# LCD_Button_LED.net
KiCad netlist of a schematic drawn in Altium Designer
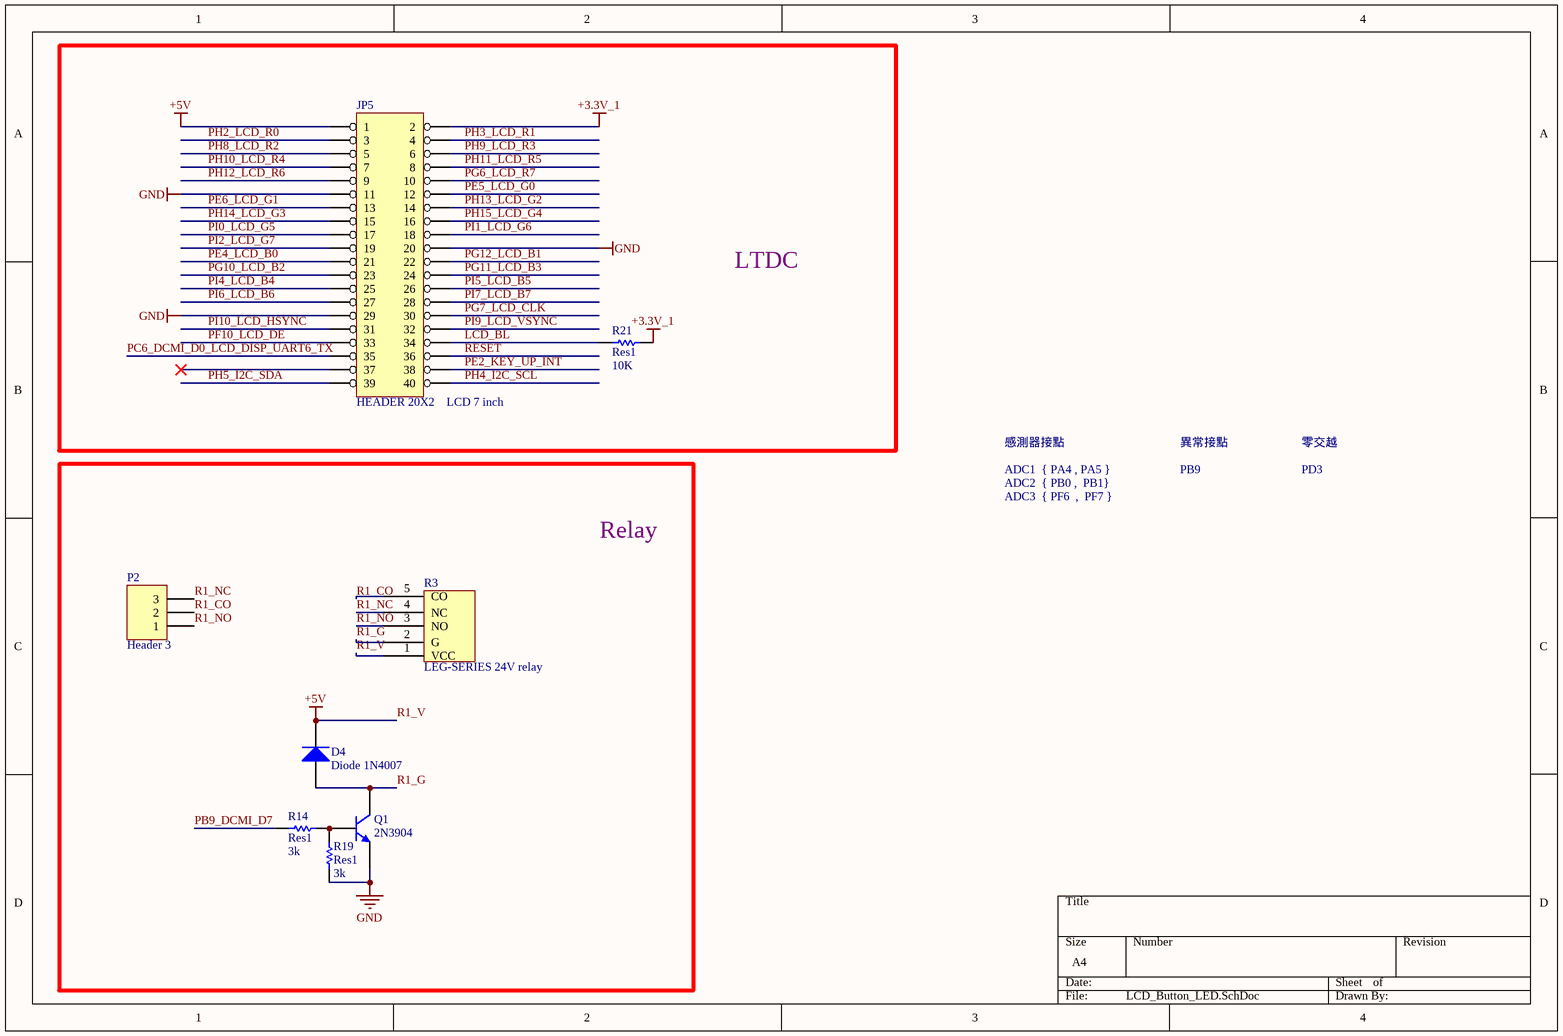
[diagram p0: LCD_Button_LED.SchDoc]

(export (version "E")
  (design (tool "Eeschema 10.0.6"))
  (components
    (comp (ref "D4")
      (value "Diode 1N4007")
      (footprint "DO-41")
      (description "High Conductance Fast Diode")
      (fields (field (name "PUBLISHER") "Altium Limited"))
      (libsource (lib "Miscellaneous Devices") (part "Diode 1N914"))
    )
    (comp (ref "JP5")
      (value "HEADER 20X2    LCD 7 inch")
      (footprint "HDR2X20")
      (libsource (lib "YB070WVHB01-50O-E1-SCH") (part "HEADER 20X2"))
    )
    (comp (ref "P2")
      (value "Header 3")
      (footprint "歐式端子*3p")
      (description "Header, 3-Pin")
      (fields (field (name "PUBLISHER") "Altium Limited"))
      (libsource (lib "Miscellaneous Connectors") (part "Header 3"))
    )
    (comp (ref "Q1")
      (value "2N3904")
      (footprint "TO-92A")
      (description "NPN General Purpose Amplifier")
      (fields (field (name "PUBLISHER") "Altium Limited"))
      (libsource (lib "Miscellaneous Devices") (part "2N3904"))
    )
    (comp (ref "R3")
      (value "LEG-SERIES 24V relay")
      (footprint "LEG-SERIES 5V")
      (libsource (lib "lib-KJ") (part "LEG-SERIES 5V relay"))
    )
    (comp (ref "R14")
      (value "Res1")
      (footprint "0805_C")
      (description "Resistor")
      (fields (field (name "ALTIUM_VALUE") "3k") (field (name "PUBLISHER") "Altium Limited"))
      (libsource (lib "Miscellaneous Devices") (part "Res1"))
    )
    (comp (ref "R19")
      (value "Res1")
      (footprint "0805_C")
      (description "Resistor")
      (fields (field (name "ALTIUM_VALUE") "3k") (field (name "PUBLISHER") "Altium Limited"))
      (libsource (lib "Miscellaneous Devices") (part "Res1"))
    )
    (comp (ref "R21")
      (value "Res1")
      (footprint "0805_C")
      (description "Resistor")
      (fields (field (name "ALTIUM_VALUE") "10K") (field (name "PUBLISHER") "Altium Limited"))
      (libsource (lib "Miscellaneous Devices") (part "Res1"))
    )
  )
  (nets
    (net (code "1") (name "+3.3V_1") (class "Default")
      (node (ref "JP5") (pin "2") (pinfunction "2_2") (pintype "passive"))
      (node (ref "R21") (pin "1") (pinfunction "1_1") (pintype "passive"))
    )
    (net (code "2") (name "+5V") (class "Default")
      (node (ref "D4") (pin "2") (pinfunction "K_2") (pintype "passive"))
      (node (ref "JP5") (pin "1") (pinfunction "1_1") (pintype "passive"))
      (node (ref "R3") (pin "1") (pinfunction "VCC_1") (pintype "passive"))
    )
    (net (code "3") (name "/LCD_BL") (class "Default")
      (node (ref "JP5") (pin "34") (pinfunction "34_34") (pintype "passive"))
      (node (ref "R21") (pin "2") (pinfunction "2_2") (pintype "passive"))
    )
    (net (code "4") (name "/PB9_DCMI_D7") (class "Default")
      (node (ref "R14") (pin "1") (pinfunction "1_1") (pintype "passive"))
    )
    (net (code "5") (name "/PC6_DCMI_D0_LCD_DISP_UART6_TX") (class "Default")
      (node (ref "JP5") (pin "35") (pinfunction "35_35") (pintype "passive"))
    )
    (net (code "6") (name "/PE2_KEY_UP_INT") (class "Default")
      (node (ref "JP5") (pin "38") (pinfunction "38_38") (pintype "passive"))
    )
    (net (code "7") (name "/PE4_LCD_B0") (class "Default")
      (node (ref "JP5") (pin "21") (pinfunction "21_21") (pintype "passive"))
    )
    (net (code "8") (name "/PE5_LCD_G0") (class "Default")
      (node (ref "JP5") (pin "12") (pinfunction "12_12") (pintype "passive"))
    )
    (net (code "9") (name "/PE6_LCD_G1") (class "Default")
      (node (ref "JP5") (pin "13") (pinfunction "13_13") (pintype "passive"))
    )
    (net (code "10") (name "/PF10_LCD_DE") (class "Default")
      (node (ref "JP5") (pin "33") (pinfunction "33_33") (pintype "passive"))
    )
    (net (code "11") (name "/PG6_LCD_R7") (class "Default")
      (node (ref "JP5") (pin "10") (pinfunction "10_10") (pintype "passive"))
    )
    (net (code "12") (name "/PG7_LCD_CLK") (class "Default")
      (node (ref "JP5") (pin "30") (pinfunction "30_30") (pintype "passive"))
    )
    (net (code "13") (name "/PG10_LCD_B2") (class "Default")
      (node (ref "JP5") (pin "23") (pinfunction "23_23") (pintype "passive"))
    )
    (net (code "14") (name "/PG11_LCD_B3") (class "Default")
      (node (ref "JP5") (pin "24") (pinfunction "24_24") (pintype "passive"))
    )
    (net (code "15") (name "/PG12_LCD_B1") (class "Default")
      (node (ref "JP5") (pin "22") (pinfunction "22_22") (pintype "passive"))
    )
    (net (code "16") (name "/PH2_LCD_R0") (class "Default")
      (node (ref "JP5") (pin "3") (pinfunction "3_3") (pintype "passive"))
    )
    (net (code "17") (name "/PH3_LCD_R1") (class "Default")
      (node (ref "JP5") (pin "4") (pinfunction "4_4") (pintype "passive"))
    )
    (net (code "18") (name "/PH4_I2C_SCL") (class "Default")
      (node (ref "JP5") (pin "40") (pinfunction "40_40") (pintype "passive"))
    )
    (net (code "19") (name "/PH5_I2C_SDA") (class "Default")
      (node (ref "JP5") (pin "39") (pinfunction "39_39") (pintype "passive"))
    )
    (net (code "20") (name "/PH8_LCD_R2") (class "Default")
      (node (ref "JP5") (pin "5") (pinfunction "5_5") (pintype "passive"))
    )
    (net (code "21") (name "/PH9_LCD_R3") (class "Default")
      (node (ref "JP5") (pin "6") (pinfunction "6_6") (pintype "passive"))
    )
    (net (code "22") (name "/PH10_LCD_R4") (class "Default")
      (node (ref "JP5") (pin "7") (pinfunction "7_7") (pintype "passive"))
    )
    (net (code "23") (name "/PH11_LCD_R5") (class "Default")
      (node (ref "JP5") (pin "8") (pinfunction "8_8") (pintype "passive"))
    )
    (net (code "24") (name "/PH12_LCD_R6") (class "Default")
      (node (ref "JP5") (pin "9") (pinfunction "9_9") (pintype "passive"))
    )
    (net (code "25") (name "/PH13_LCD_G2") (class "Default")
      (node (ref "JP5") (pin "14") (pinfunction "14_14") (pintype "passive"))
    )
    (net (code "26") (name "/PH14_LCD_G3") (class "Default")
      (node (ref "JP5") (pin "15") (pinfunction "15_15") (pintype "passive"))
    )
    (net (code "27") (name "/PH15_LCD_G4") (class "Default")
      (node (ref "JP5") (pin "16") (pinfunction "16_16") (pintype "passive"))
    )
    (net (code "28") (name "/PI0_LCD_G5") (class "Default")
      (node (ref "JP5") (pin "17") (pinfunction "17_17") (pintype "passive"))
    )
    (net (code "29") (name "/PI1_LCD_G6") (class "Default")
      (node (ref "JP5") (pin "18") (pinfunction "18_18") (pintype "passive"))
    )
    (net (code "30") (name "/PI2_LCD_G7") (class "Default")
      (node (ref "JP5") (pin "19") (pinfunction "19_19") (pintype "passive"))
    )
    (net (code "31") (name "/PI4_LCD_B4") (class "Default")
      (node (ref "JP5") (pin "25") (pinfunction "25_25") (pintype "passive"))
    )
    (net (code "32") (name "/PI5_LCD_B5") (class "Default")
      (node (ref "JP5") (pin "26") (pinfunction "26_26") (pintype "passive"))
    )
    (net (code "33") (name "/PI6_LCD_B6") (class "Default")
      (node (ref "JP5") (pin "27") (pinfunction "27_27") (pintype "passive"))
    )
    (net (code "34") (name "/PI7_LCD_B7") (class "Default")
      (node (ref "JP5") (pin "28") (pinfunction "28_28") (pintype "passive"))
    )
    (net (code "35") (name "/PI9_LCD_VSYNC") (class "Default")
      (node (ref "JP5") (pin "32") (pinfunction "32_32") (pintype "passive"))
    )
    (net (code "36") (name "/PI10_LCD_HSYNC") (class "Default")
      (node (ref "JP5") (pin "31") (pinfunction "31_31") (pintype "passive"))
    )
    (net (code "37") (name "/R1_CO") (class "Default")
      (node (ref "P2") (pin "2") (pinfunction "2_2") (pintype "passive"))
      (node (ref "R3") (pin "5") (pinfunction "CO_5") (pintype "passive"))
    )
    (net (code "38") (name "/R1_G") (class "Default")
      (node (ref "D4") (pin "1") (pinfunction "A_1") (pintype "passive"))
      (node (ref "Q1") (pin "3") (pinfunction "C_3") (pintype "passive"))
      (node (ref "R3") (pin "2") (pinfunction "G_2") (pintype "passive"))
    )
    (net (code "39") (name "/R1_NC") (class "Default")
      (node (ref "P2") (pin "3") (pinfunction "3_3") (pintype "passive"))
      (node (ref "R3") (pin "4") (pinfunction "NC_4") (pintype "passive"))
    )
    (net (code "40") (name "/R1_NO") (class "Default")
      (node (ref "P2") (pin "1") (pinfunction "1_1") (pintype "passive"))
      (node (ref "R3") (pin "3") (pinfunction "NO_3") (pintype "passive"))
    )
    (net (code "41") (name "/RESET") (class "Default")
      (node (ref "JP5") (pin "36") (pinfunction "36_36") (pintype "passive"))
    )
    (net (code "42") (name "GND") (class "Default")
      (node (ref "JP5") (pin "11") (pinfunction "11_11") (pintype "passive"))
      (node (ref "JP5") (pin "20") (pinfunction "20_20") (pintype "passive"))
      (node (ref "JP5") (pin "29") (pinfunction "29_29") (pintype "passive"))
      (node (ref "Q1") (pin "1") (pinfunction "E_1") (pintype "passive"))
      (node (ref "R19") (pin "1") (pinfunction "1_1") (pintype "passive"))
    )
    (net (code "43") (name "Net-(Q1-B)") (class "Default")
      (node (ref "Q1") (pin "2") (pinfunction "B_2") (pintype "passive"))
      (node (ref "R14") (pin "2") (pinfunction "2_2") (pintype "passive"))
      (node (ref "R19") (pin "2") (pinfunction "2_2") (pintype "passive"))
    )
    (net (code "44") (name "unconnected-(JP5-Pad37)") (class "Default")
      (node (ref "JP5") (pin "37") (pinfunction "37_37") (pintype "passive+no_connect"))
    )
  )
)
